# monroe-half-hi.net
KiCad netlist of a schematic drawn in EAGLE
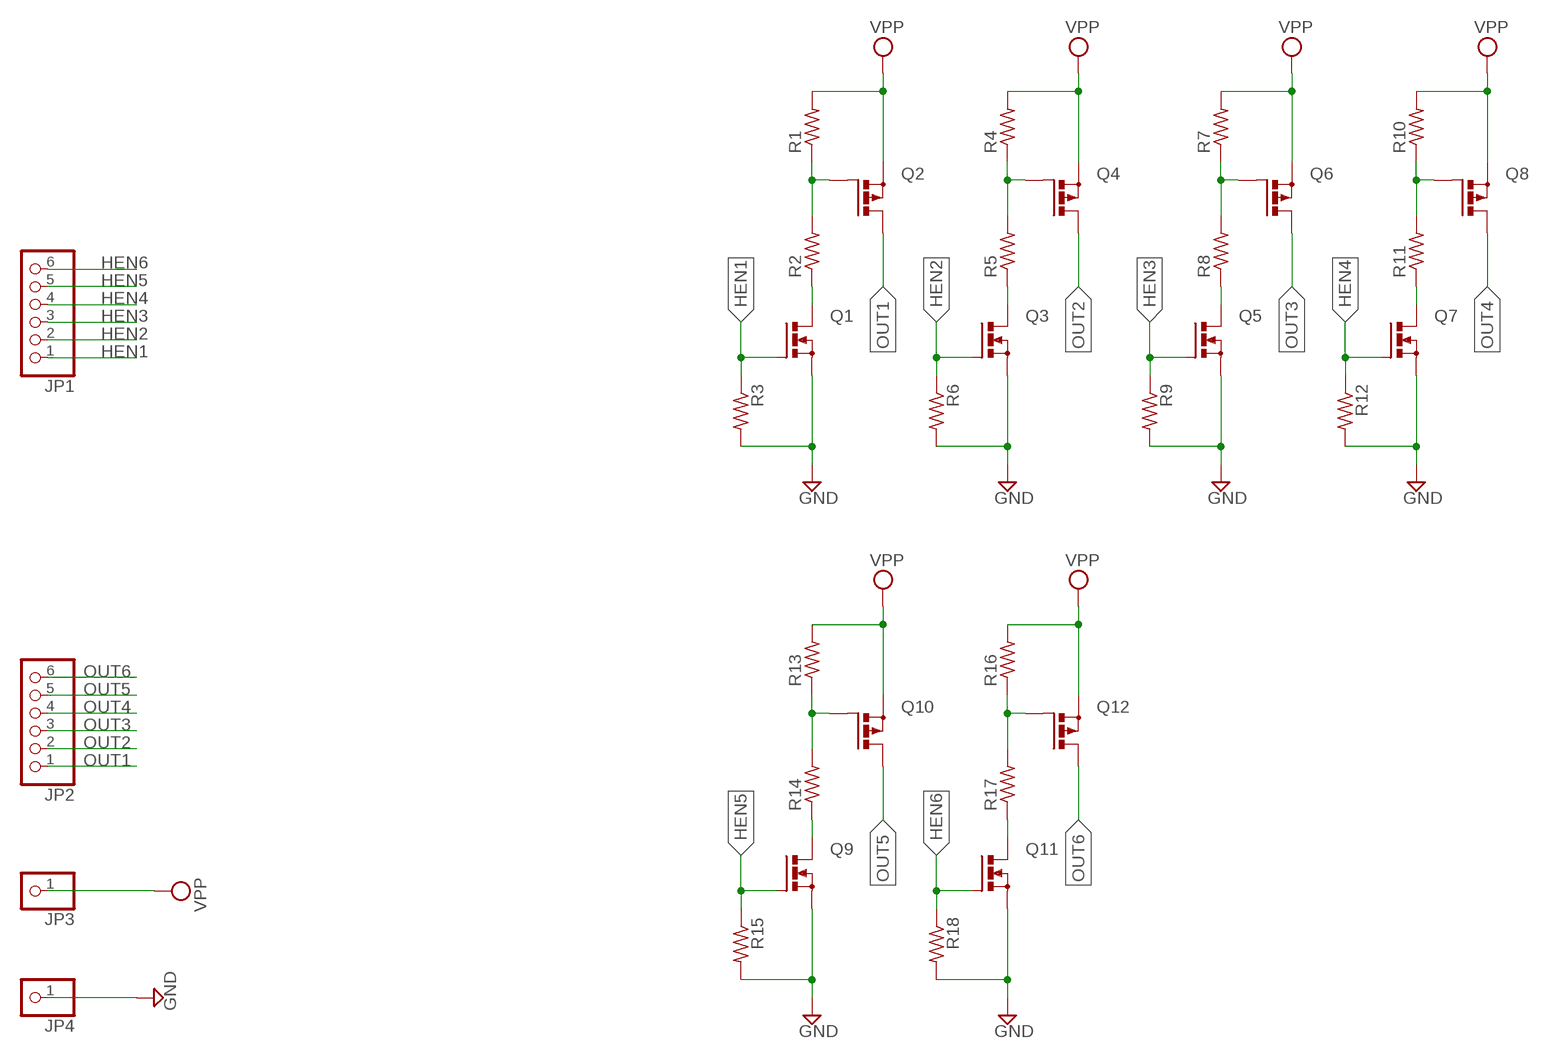
[diagram p0: schematic, sheet 1]

(export (version "E")
  (design (tool "Eeschema 10.0.6"))
  (components
    (comp (ref "JP1")
      (value "PINHD-1X6")
      (footprint "eagle-import:1X06")
      (libsource (lib "eagle-import") (part "PINHD-1X6"))
    )
    (comp (ref "JP2")
      (value "PINHD-1X6")
      (footprint "eagle-import:1X06")
      (libsource (lib "eagle-import") (part "PINHD-1X6"))
    )
    (comp (ref "JP3")
      (value "PINHD-1X1")
      (footprint "eagle-import:1X01")
      (libsource (lib "eagle-import") (part "PINHD-1X1"))
    )
    (comp (ref "JP4")
      (value "PINHD-1X1")
      (footprint "eagle-import:1X01")
      (libsource (lib "eagle-import") (part "PINHD-1X1"))
    )
    (comp (ref "Q1")
      (value "PMOSFET_NTO220BV")
      (footprint "eagle-import:TO220BV")
      (libsource (lib "eagle-import") (part "PMOSFET_NTO220BV"))
    )
    (comp (ref "Q2")
      (value "PMOSFET_PTO220BV")
      (footprint "eagle-import:TO220BV")
      (libsource (lib "eagle-import") (part "PMOSFET_PTO220BV"))
    )
    (comp (ref "Q3")
      (value "PMOSFET_NTO220BV")
      (footprint "eagle-import:TO220BV")
      (libsource (lib "eagle-import") (part "PMOSFET_NTO220BV"))
    )
    (comp (ref "Q4")
      (value "PMOSFET_PTO220BV")
      (footprint "eagle-import:TO220BV")
      (libsource (lib "eagle-import") (part "PMOSFET_PTO220BV"))
    )
    (comp (ref "Q5")
      (value "PMOSFET_NTO220BV")
      (footprint "eagle-import:TO220BV")
      (libsource (lib "eagle-import") (part "PMOSFET_NTO220BV"))
    )
    (comp (ref "Q6")
      (value "PMOSFET_PTO220BV")
      (footprint "eagle-import:TO220BV")
      (libsource (lib "eagle-import") (part "PMOSFET_PTO220BV"))
    )
    (comp (ref "Q7")
      (value "PMOSFET_NTO220BV")
      (footprint "eagle-import:TO220BV")
      (libsource (lib "eagle-import") (part "PMOSFET_NTO220BV"))
    )
    (comp (ref "Q8")
      (value "PMOSFET_PTO220BV")
      (footprint "eagle-import:TO220BV")
      (libsource (lib "eagle-import") (part "PMOSFET_PTO220BV"))
    )
    (comp (ref "Q9")
      (value "PMOSFET_NTO220BV")
      (footprint "eagle-import:TO220BV")
      (libsource (lib "eagle-import") (part "PMOSFET_NTO220BV"))
    )
    (comp (ref "Q10")
      (value "PMOSFET_PTO220BV")
      (footprint "eagle-import:TO220BV")
      (libsource (lib "eagle-import") (part "PMOSFET_PTO220BV"))
    )
    (comp (ref "Q11")
      (value "PMOSFET_NTO220BV")
      (footprint "eagle-import:TO220BV")
      (libsource (lib "eagle-import") (part "PMOSFET_NTO220BV"))
    )
    (comp (ref "Q12")
      (value "PMOSFET_PTO220BV")
      (footprint "eagle-import:TO220BV")
      (libsource (lib "eagle-import") (part "PMOSFET_PTO220BV"))
    )
    (comp (ref "R1")
      (value "R-US_0207/5V")
      (footprint "eagle-import:0207_5V")
      (libsource (lib "eagle-import") (part "R-US_0207/5V"))
    )
    (comp (ref "R2")
      (value "R-US_0207/10")
      (footprint "eagle-import:0207_10")
      (libsource (lib "eagle-import") (part "resistor_R-US_0207/10"))
    )
    (comp (ref "R3")
      (value "R-US_0207/5V")
      (footprint "eagle-import:0207_5V")
      (libsource (lib "eagle-import") (part "R-US_0207/5V"))
    )
    (comp (ref "R4")
      (value "R-US_0207/5V")
      (footprint "eagle-import:0207_5V")
      (libsource (lib "eagle-import") (part "R-US_0207/5V"))
    )
    (comp (ref "R5")
      (value "R-US_0207/10")
      (footprint "eagle-import:0207_10")
      (libsource (lib "eagle-import") (part "resistor_R-US_0207/10"))
    )
    (comp (ref "R6")
      (value "R-US_0207/5V")
      (footprint "eagle-import:0207_5V")
      (libsource (lib "eagle-import") (part "R-US_0207/5V"))
    )
    (comp (ref "R7")
      (value "R-US_0207/5V")
      (footprint "eagle-import:0207_5V")
      (libsource (lib "eagle-import") (part "R-US_0207/5V"))
    )
    (comp (ref "R8")
      (value "R-US_0207/10")
      (footprint "eagle-import:0207_10")
      (libsource (lib "eagle-import") (part "resistor_R-US_0207/10"))
    )
    (comp (ref "R9")
      (value "R-US_0207/5V")
      (footprint "eagle-import:0207_5V")
      (libsource (lib "eagle-import") (part "R-US_0207/5V"))
    )
    (comp (ref "R10")
      (value "R-US_0207/5V")
      (footprint "eagle-import:0207_5V")
      (libsource (lib "eagle-import") (part "R-US_0207/5V"))
    )
    (comp (ref "R11")
      (value "R-US_0207/10")
      (footprint "eagle-import:0207_10")
      (libsource (lib "eagle-import") (part "resistor_R-US_0207/10"))
    )
    (comp (ref "R12")
      (value "R-US_0207/5V")
      (footprint "eagle-import:0207_5V")
      (libsource (lib "eagle-import") (part "R-US_0207/5V"))
    )
    (comp (ref "R13")
      (value "R-US_0207/5V")
      (footprint "eagle-import:0207_5V")
      (libsource (lib "eagle-import") (part "R-US_0207/5V"))
    )
    (comp (ref "R14")
      (value "R-US_0207/10")
      (footprint "eagle-import:0207_10")
      (libsource (lib "eagle-import") (part "resistor_R-US_0207/10"))
    )
    (comp (ref "R15")
      (value "R-US_0207/5V")
      (footprint "eagle-import:0207_5V")
      (libsource (lib "eagle-import") (part "R-US_0207/5V"))
    )
    (comp (ref "R16")
      (value "R-US_0207/5V")
      (footprint "eagle-import:0207_5V")
      (libsource (lib "eagle-import") (part "R-US_0207/5V"))
    )
    (comp (ref "R17")
      (value "R-US_0207/10")
      (footprint "eagle-import:0207_10")
      (libsource (lib "eagle-import") (part "resistor_R-US_0207/10"))
    )
    (comp (ref "R18")
      (value "R-US_0207/5V")
      (footprint "eagle-import:0207_5V")
      (libsource (lib "eagle-import") (part "R-US_0207/5V"))
    )
  )
  (nets
    (net (code "1") (name "GND") (class "Default")
      (node (ref "JP4") (pin "1") (pinfunction "1_1") (pintype "passive"))
      (node (ref "Q1") (pin "S") (pinfunction "S_S") (pintype "passive"))
      (node (ref "Q11") (pin "S") (pinfunction "S_S") (pintype "passive"))
      (node (ref "Q3") (pin "S") (pinfunction "S_S") (pintype "passive"))
      (node (ref "Q5") (pin "S") (pinfunction "S_S") (pintype "passive"))
      (node (ref "Q7") (pin "S") (pinfunction "S_S") (pintype "passive"))
      (node (ref "Q9") (pin "S") (pinfunction "S_S") (pintype "passive"))
      (node (ref "R12") (pin "2") (pinfunction "2_2") (pintype "passive"))
      (node (ref "R15") (pin "2") (pinfunction "2_2") (pintype "passive"))
      (node (ref "R18") (pin "2") (pinfunction "2_2") (pintype "passive"))
      (node (ref "R3") (pin "2") (pinfunction "2_2") (pintype "passive"))
      (node (ref "R6") (pin "2") (pinfunction "2_2") (pintype "passive"))
      (node (ref "R9") (pin "2") (pinfunction "2_2") (pintype "passive"))
    )
    (net (code "2") (name "HEN1") (class "Default")
      (node (ref "JP1") (pin "1") (pinfunction "1_1") (pintype "passive"))
      (node (ref "Q1") (pin "G") (pinfunction "G_G") (pintype "passive"))
      (node (ref "R3") (pin "1") (pinfunction "1_1") (pintype "passive"))
    )
    (net (code "3") (name "HEN2") (class "Default")
      (node (ref "JP1") (pin "2") (pinfunction "2_2") (pintype "passive"))
      (node (ref "Q3") (pin "G") (pinfunction "G_G") (pintype "passive"))
      (node (ref "R6") (pin "1") (pinfunction "1_1") (pintype "passive"))
    )
    (net (code "4") (name "HEN3") (class "Default")
      (node (ref "JP1") (pin "3") (pinfunction "3_3") (pintype "passive"))
      (node (ref "Q5") (pin "G") (pinfunction "G_G") (pintype "passive"))
      (node (ref "R9") (pin "1") (pinfunction "1_1") (pintype "passive"))
    )
    (net (code "5") (name "HEN4") (class "Default")
      (node (ref "JP1") (pin "4") (pinfunction "4_4") (pintype "passive"))
      (node (ref "Q7") (pin "G") (pinfunction "G_G") (pintype "passive"))
      (node (ref "R12") (pin "1") (pinfunction "1_1") (pintype "passive"))
    )
    (net (code "6") (name "HEN5") (class "Default")
      (node (ref "JP1") (pin "5") (pinfunction "5_5") (pintype "passive"))
      (node (ref "Q9") (pin "G") (pinfunction "G_G") (pintype "passive"))
      (node (ref "R15") (pin "1") (pinfunction "1_1") (pintype "passive"))
    )
    (net (code "7") (name "HEN6") (class "Default")
      (node (ref "JP1") (pin "6") (pinfunction "6_6") (pintype "passive"))
      (node (ref "Q11") (pin "G") (pinfunction "G_G") (pintype "passive"))
      (node (ref "R18") (pin "1") (pinfunction "1_1") (pintype "passive"))
    )
    (net (code "8") (name "Net-(Q1-PadD)") (class "Default")
      (node (ref "Q1") (pin "D") (pinfunction "D_D") (pintype "passive"))
      (node (ref "R2") (pin "1") (pinfunction "1_1") (pintype "passive"))
    )
    (net (code "9") (name "Net-(Q2-PadG)") (class "Default")
      (node (ref "Q2") (pin "G") (pinfunction "G_G") (pintype "passive"))
      (node (ref "R1") (pin "1") (pinfunction "1_1") (pintype "passive"))
      (node (ref "R2") (pin "2") (pinfunction "2_2") (pintype "passive"))
    )
    (net (code "10") (name "Net-(Q3-PadD)") (class "Default")
      (node (ref "Q3") (pin "D") (pinfunction "D_D") (pintype "passive"))
      (node (ref "R5") (pin "1") (pinfunction "1_1") (pintype "passive"))
    )
    (net (code "11") (name "Net-(Q4-PadG)") (class "Default")
      (node (ref "Q4") (pin "G") (pinfunction "G_G") (pintype "passive"))
      (node (ref "R4") (pin "1") (pinfunction "1_1") (pintype "passive"))
      (node (ref "R5") (pin "2") (pinfunction "2_2") (pintype "passive"))
    )
    (net (code "12") (name "Net-(Q5-PadD)") (class "Default")
      (node (ref "Q5") (pin "D") (pinfunction "D_D") (pintype "passive"))
      (node (ref "R8") (pin "1") (pinfunction "1_1") (pintype "passive"))
    )
    (net (code "13") (name "Net-(Q6-PadG)") (class "Default")
      (node (ref "Q6") (pin "G") (pinfunction "G_G") (pintype "passive"))
      (node (ref "R7") (pin "1") (pinfunction "1_1") (pintype "passive"))
      (node (ref "R8") (pin "2") (pinfunction "2_2") (pintype "passive"))
    )
    (net (code "14") (name "Net-(Q7-PadD)") (class "Default")
      (node (ref "Q7") (pin "D") (pinfunction "D_D") (pintype "passive"))
      (node (ref "R11") (pin "1") (pinfunction "1_1") (pintype "passive"))
    )
    (net (code "15") (name "Net-(Q8-PadG)") (class "Default")
      (node (ref "Q8") (pin "G") (pinfunction "G_G") (pintype "passive"))
      (node (ref "R10") (pin "1") (pinfunction "1_1") (pintype "passive"))
      (node (ref "R11") (pin "2") (pinfunction "2_2") (pintype "passive"))
    )
    (net (code "16") (name "Net-(Q9-PadD)") (class "Default")
      (node (ref "Q9") (pin "D") (pinfunction "D_D") (pintype "passive"))
      (node (ref "R14") (pin "1") (pinfunction "1_1") (pintype "passive"))
    )
    (net (code "17") (name "Net-(Q10-PadG)") (class "Default")
      (node (ref "Q10") (pin "G") (pinfunction "G_G") (pintype "passive"))
      (node (ref "R13") (pin "1") (pinfunction "1_1") (pintype "passive"))
      (node (ref "R14") (pin "2") (pinfunction "2_2") (pintype "passive"))
    )
    (net (code "18") (name "Net-(Q11-PadD)") (class "Default")
      (node (ref "Q11") (pin "D") (pinfunction "D_D") (pintype "passive"))
      (node (ref "R17") (pin "1") (pinfunction "1_1") (pintype "passive"))
    )
    (net (code "19") (name "Net-(Q12-PadG)") (class "Default")
      (node (ref "Q12") (pin "G") (pinfunction "G_G") (pintype "passive"))
      (node (ref "R16") (pin "1") (pinfunction "1_1") (pintype "passive"))
      (node (ref "R17") (pin "2") (pinfunction "2_2") (pintype "passive"))
    )
    (net (code "20") (name "OUT1") (class "Default")
      (node (ref "JP2") (pin "1") (pinfunction "1_1") (pintype "passive"))
      (node (ref "Q2") (pin "D") (pinfunction "D_D") (pintype "passive"))
    )
    (net (code "21") (name "OUT2") (class "Default")
      (node (ref "JP2") (pin "2") (pinfunction "2_2") (pintype "passive"))
      (node (ref "Q4") (pin "D") (pinfunction "D_D") (pintype "passive"))
    )
    (net (code "22") (name "OUT3") (class "Default")
      (node (ref "JP2") (pin "3") (pinfunction "3_3") (pintype "passive"))
      (node (ref "Q6") (pin "D") (pinfunction "D_D") (pintype "passive"))
    )
    (net (code "23") (name "OUT4") (class "Default")
      (node (ref "JP2") (pin "4") (pinfunction "4_4") (pintype "passive"))
      (node (ref "Q8") (pin "D") (pinfunction "D_D") (pintype "passive"))
    )
    (net (code "24") (name "OUT5") (class "Default")
      (node (ref "JP2") (pin "5") (pinfunction "5_5") (pintype "passive"))
      (node (ref "Q10") (pin "D") (pinfunction "D_D") (pintype "passive"))
    )
    (net (code "25") (name "OUT6") (class "Default")
      (node (ref "JP2") (pin "6") (pinfunction "6_6") (pintype "passive"))
      (node (ref "Q12") (pin "D") (pinfunction "D_D") (pintype "passive"))
    )
    (net (code "26") (name "VPP") (class "Default")
      (node (ref "JP3") (pin "1") (pinfunction "1_1") (pintype "passive"))
      (node (ref "Q10") (pin "S") (pinfunction "S_S") (pintype "passive"))
      (node (ref "Q12") (pin "S") (pinfunction "S_S") (pintype "passive"))
      (node (ref "Q2") (pin "S") (pinfunction "S_S") (pintype "passive"))
      (node (ref "Q4") (pin "S") (pinfunction "S_S") (pintype "passive"))
      (node (ref "Q6") (pin "S") (pinfunction "S_S") (pintype "passive"))
      (node (ref "Q8") (pin "S") (pinfunction "S_S") (pintype "passive"))
      (node (ref "R1") (pin "2") (pinfunction "2_2") (pintype "passive"))
      (node (ref "R10") (pin "2") (pinfunction "2_2") (pintype "passive"))
      (node (ref "R13") (pin "2") (pinfunction "2_2") (pintype "passive"))
      (node (ref "R16") (pin "2") (pinfunction "2_2") (pintype "passive"))
      (node (ref "R4") (pin "2") (pinfunction "2_2") (pintype "passive"))
      (node (ref "R7") (pin "2") (pinfunction "2_2") (pintype "passive"))
    )
  )
)
